# 555_Monostable_Multivibrator.net
KiCad netlist of a schematic drawn in Altium Designer
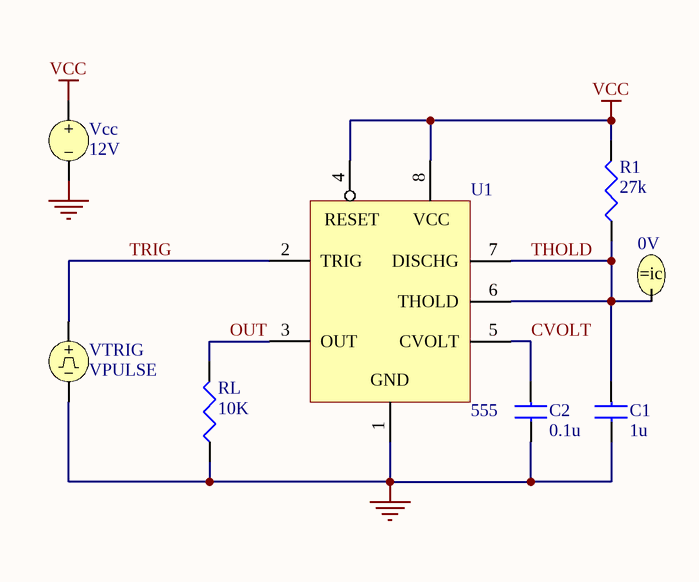
[diagram p0: 555 Monostable Multivibrator.schdoc]

(export (version "E")
  (design (tool "Eeschema 10.0.6"))
  (components
    (comp (ref "C1") (value "1u") (description "Capacitor") (libsource (lib "*") (part "CAP")))
    (comp (ref "C2") (value "0.1u") (description "Capacitor") (libsource (lib "*") (part "CAP")))
    (comp (ref "IC1")
      (value "0V")
      (description "Initial Condition")
      (fields (field (name "INITIAL VOLTAGE") "0V"))
      (libsource (lib "*") (part ".IC"))
    )
    (comp (ref "R1") (value "27k") (description "Resistor") (libsource (lib "*") (part "RES")))
    (comp (ref "RL") (value "10K") (description "Resistor") (libsource (lib "*") (part "RES")))
    (comp (ref "U1") (value "555") (description "Timer") (libsource (lib "*") (part "555")))
    (comp (ref "Vcc") (value "12V") (description "Voltage Source") (libsource (lib "*") (part "VSRC")))
    (comp (ref "VTRIG")
      (value "VPULSE")
      (description "Pulse Voltage Source")
      (libsource (lib "*") (part "VPULSE"))
    )
  )
  (nets
    (net (code "1") (name "/CVOLT") (class "Default")
      (node (ref "C2") (pin "1") (pinfunction "1_1") (pintype "passive"))
      (node (ref "U1") (pin "5") (pinfunction "CVOLT_5") (pintype "passive"))
    )
    (net (code "2") (name "/OUT") (class "Default")
      (node (ref "RL") (pin "1") (pinfunction "TOP_1") (pintype "passive"))
      (node (ref "U1") (pin "3") (pinfunction "OUT_3") (pintype "passive"))
    )
    (net (code "3") (name "/THOLD") (class "Default")
      (node (ref "C1") (pin "1") (pinfunction "1_1") (pintype "passive"))
      (node (ref "IC1") (pin "1") (pinfunction "1_1") (pintype "passive"))
      (node (ref "R1") (pin "2") (pinfunction "BOT_2") (pintype "passive"))
      (node (ref "U1") (pin "6") (pinfunction "THOLD_6") (pintype "passive"))
      (node (ref "U1") (pin "7") (pinfunction "DISCHG_7") (pintype "passive"))
    )
    (net (code "4") (name "/TRIG") (class "Default")
      (node (ref "U1") (pin "2") (pinfunction "TRIG_2") (pintype "passive"))
      (node (ref "VTRIG") (pin "1") (pinfunction "1_1") (pintype "passive"))
    )
    (net (code "5") (name "GND") (class "Default")
      (node (ref "C1") (pin "2") (pinfunction "2_2") (pintype "passive"))
      (node (ref "C2") (pin "2") (pinfunction "2_2") (pintype "passive"))
      (node (ref "RL") (pin "2") (pinfunction "BOT_2") (pintype "passive"))
      (node (ref "U1") (pin "1") (pinfunction "GND_1") (pintype "passive"))
      (node (ref "VTRIG") (pin "2") (pinfunction "2_2") (pintype "passive"))
      (node (ref "Vcc") (pin "2") (pinfunction "2_2") (pintype "passive"))
    )
    (net (code "6") (name "VCC") (class "Default")
      (node (ref "R1") (pin "1") (pinfunction "TOP_1") (pintype "passive"))
      (node (ref "U1") (pin "4") (pinfunction "RESET_4") (pintype "passive"))
      (node (ref "U1") (pin "8") (pinfunction "VCC_8") (pintype "passive"))
      (node (ref "Vcc") (pin "1") (pinfunction "1_1") (pintype "passive"))
    )
  )
)
